# PCB-REMCON-E.net
KiCad netlist of a schematic drawn in EAGLE
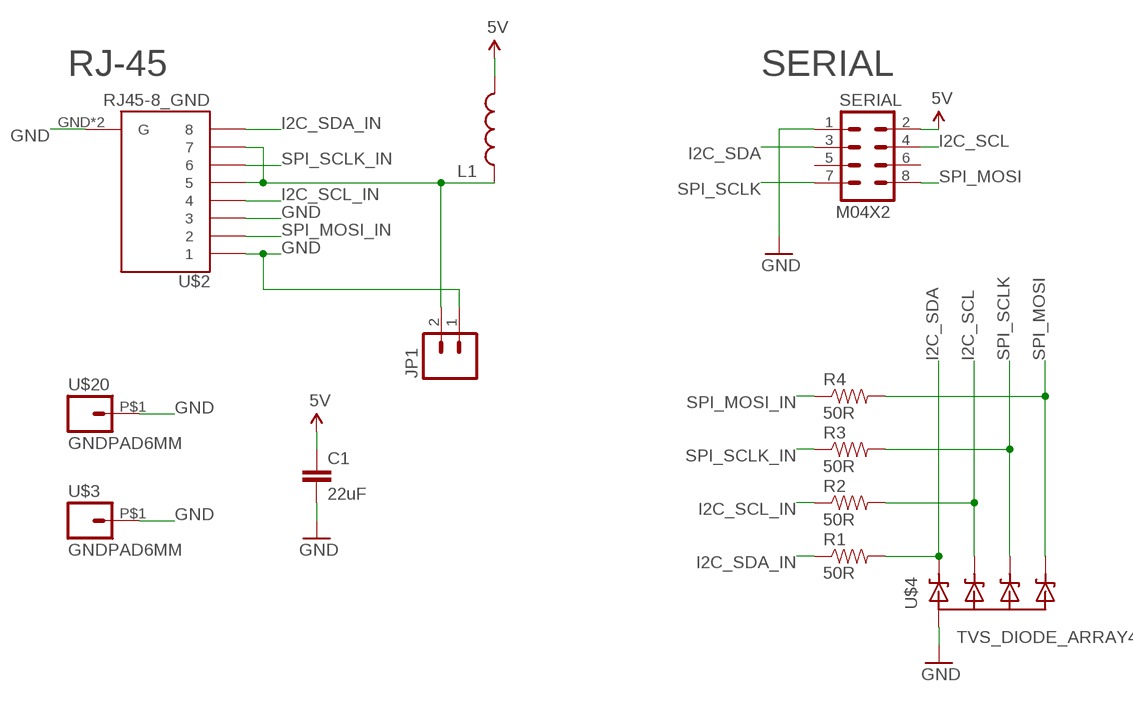
[diagram p0: schematic, sheet 1]

(export (version "E")
  (design (tool "Eeschema 10.0.6"))
  (components
    (comp (ref "C1")
      (value "22uF")
      (footprint "eagle-import:0805")
      (libsource (lib "eagle-import") (part "CAP0805"))
    )
    (comp (ref "JP1")
      (value "M02PTH")
      (footprint "eagle-import:1X02")
      (libsource (lib "eagle-import") (part "M02PTH"))
    )
    (comp (ref "L1")
      (value "INDUCTOR0805")
      (footprint "eagle-import:0805")
      (libsource (lib "eagle-import") (part "INDUCTOR0805"))
    )
    (comp (ref "R1")
      (value "50R")
      (footprint "eagle-import:0603-RES")
      (libsource (lib "eagle-import") (part "RESISTOR0603-RES"))
    )
    (comp (ref "R2")
      (value "50R")
      (footprint "eagle-import:0603-RES")
      (libsource (lib "eagle-import") (part "RESISTOR0603-RES"))
    )
    (comp (ref "R3")
      (value "50R")
      (footprint "eagle-import:0603-RES")
      (libsource (lib "eagle-import") (part "RESISTOR0603-RES"))
    )
    (comp (ref "R4")
      (value "50R")
      (footprint "eagle-import:0603-RES")
      (libsource (lib "eagle-import") (part "RESISTOR0603-RES"))
    )
    (comp (ref "SERIAL")
      (value "M04X2")
      (footprint "eagle-import:2X4")
      (libsource (lib "eagle-import") (part "M04X2"))
    )
    (comp (ref "U$2")
      (value "RJ45-8_GND")
      (footprint "eagle-import:RJ45-8_GND")
      (libsource (lib "eagle-import") (part "RJ45-8_GND"))
    )
    (comp (ref "U$3")
      (value "GNDPAD6MM")
      (footprint "eagle-import:3.2MMPAD6MM")
      (libsource (lib "eagle-import") (part "GNDPAD6MM"))
    )
    (comp (ref "U$4")
      (value "TVS_DIODE_ARRAY4")
      (footprint "eagle-import:SOT23-6L")
      (libsource (lib "eagle-import") (part "TVS_DIODE_ARRAY4"))
    )
    (comp (ref "U$20")
      (value "GNDPAD6MM")
      (footprint "eagle-import:3.2MMPAD6MM")
      (libsource (lib "eagle-import") (part "GNDPAD6MM"))
    )
  )
  (nets
    (net (code "1") (name "/I2C_SCL") (class "Default")
      (node (ref "R2") (pin "2") (pinfunction "2_2") (pintype "passive"))
      (node (ref "SERIAL") (pin "4") (pinfunction "4_4") (pintype "passive"))
      (node (ref "U$4") (pin "3") (pinfunction "B_3") (pintype "passive"))
    )
    (net (code "2") (name "/I2C_SCL_IN") (class "Default")
      (node (ref "R2") (pin "1") (pinfunction "1_1") (pintype "passive"))
      (node (ref "U$2") (pin "4") (pinfunction "4_4") (pintype "bidirectional"))
    )
    (net (code "3") (name "/I2C_SDA") (class "Default")
      (node (ref "R1") (pin "2") (pinfunction "2_2") (pintype "passive"))
      (node (ref "SERIAL") (pin "3") (pinfunction "3_3") (pintype "passive"))
      (node (ref "U$4") (pin "1") (pinfunction "A_1") (pintype "passive"))
    )
    (net (code "4") (name "/I2C_SDA_IN") (class "Default")
      (node (ref "R1") (pin "1") (pinfunction "1_1") (pintype "passive"))
      (node (ref "U$2") (pin "8") (pinfunction "8_8") (pintype "bidirectional"))
    )
    (net (code "5") (name "/SPI_MOSI") (class "Default")
      (node (ref "R4") (pin "2") (pinfunction "2_2") (pintype "passive"))
      (node (ref "SERIAL") (pin "8") (pinfunction "8_8") (pintype "passive"))
      (node (ref "U$4") (pin "6") (pinfunction "D_6") (pintype "passive"))
    )
    (net (code "6") (name "/SPI_MOSI_IN") (class "Default")
      (node (ref "R4") (pin "1") (pinfunction "1_1") (pintype "passive"))
      (node (ref "U$2") (pin "2") (pinfunction "2_2") (pintype "bidirectional"))
    )
    (net (code "7") (name "/SPI_SCLK") (class "Default")
      (node (ref "R3") (pin "2") (pinfunction "2_2") (pintype "passive"))
      (node (ref "SERIAL") (pin "7") (pinfunction "7_7") (pintype "passive"))
      (node (ref "U$4") (pin "4") (pinfunction "C_4") (pintype "passive"))
    )
    (net (code "8") (name "/SPI_SCLK_IN") (class "Default")
      (node (ref "R3") (pin "1") (pinfunction "1_1") (pintype "passive"))
      (node (ref "U$2") (pin "6") (pinfunction "6_6") (pintype "bidirectional"))
    )
    (net (code "9") (name "5V") (class "Default")
      (node (ref "C1") (pin "1") (pinfunction "1_1") (pintype "passive"))
      (node (ref "L1") (pin "2") (pinfunction "2_2") (pintype "passive"))
      (node (ref "SERIAL") (pin "2") (pinfunction "2_2") (pintype "passive"))
    )
    (net (code "10") (name "GND") (class "Default")
      (node (ref "C1") (pin "2") (pinfunction "2_2") (pintype "passive"))
      (node (ref "JP1") (pin "1") (pinfunction "1_1") (pintype "passive"))
      (node (ref "SERIAL") (pin "1") (pinfunction "1_1") (pintype "passive"))
      (node (ref "U$2") (pin "1") (pinfunction "1_1") (pintype "bidirectional"))
      (node (ref "U$2") (pin "3") (pinfunction "3_3") (pintype "bidirectional"))
      (node (ref "U$2") (pin "GND") (pinfunction "G_GND") (pintype "power_in"))
      (node (ref "U$2") (pin "GND1") (pinfunction "G_GND1") (pintype "power_in"))
      (node (ref "U$20") (pin "P$1") (pinfunction "1_P$1") (pintype "passive"))
      (node (ref "U$3") (pin "P$1") (pinfunction "1_P$1") (pintype "passive"))
      (node (ref "U$4") (pin "2") (pinfunction "GND_2") (pintype "passive"))
      (node (ref "U$4") (pin "5") (pinfunction "GND_5") (pintype "passive"))
    )
    (net (code "11") (name "Net-(JP1-Pad2)") (class "Default")
      (node (ref "JP1") (pin "2") (pinfunction "2_2") (pintype "passive"))
      (node (ref "L1") (pin "1") (pinfunction "1_1") (pintype "passive"))
      (node (ref "U$2") (pin "5") (pinfunction "5_5") (pintype "bidirectional"))
      (node (ref "U$2") (pin "7") (pinfunction "7_7") (pintype "bidirectional"))
    )
    (net (code "12") (name "unconnected-(SERIAL-Pad5)") (class "Default")
      (node (ref "SERIAL") (pin "5") (pinfunction "5_5") (pintype "passive"))
    )
    (net (code "13") (name "unconnected-(SERIAL-Pad6)") (class "Default")
      (node (ref "SERIAL") (pin "6") (pinfunction "6_6") (pintype "passive"))
    )
  )
)
